# connectors.net
KiCad netlist of a schematic drawn in Altium Designer
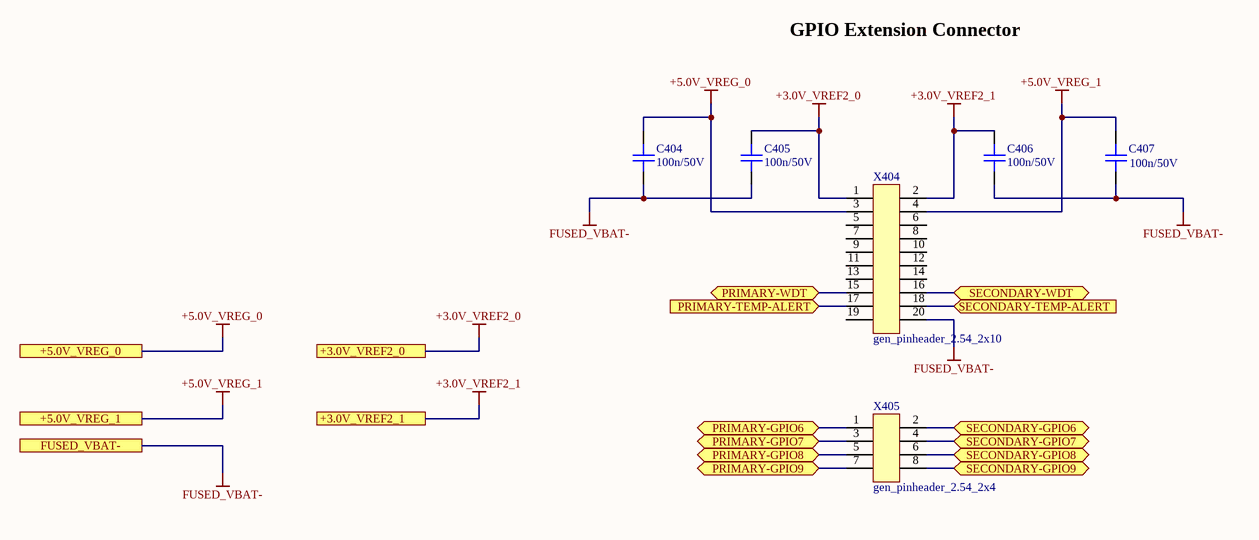
[diagram p0: connectors.SchDoc]

(export (version "E")
  (design (tool "Eeschema 10.0.6"))
  (components
    (comp (ref "C404")
      (value "100n/50V")
      (footprint "CAPC1608X08N")
      (description "MLCC")
      (fields (field (name "PART NUMBER") "gen_C_ceramic_100n_50V_X7R_0603"))
      (libsource (lib "OE750") (part "C"))
    )
    (comp (ref "C405")
      (value "100n/50V")
      (footprint "CAPC1608X08N")
      (description "MLCC")
      (fields (field (name "PART NUMBER") "gen_C_ceramic_100n_50V_X7R_0603"))
      (libsource (lib "OE750") (part "C"))
    )
    (comp (ref "C406")
      (value "100n/50V")
      (footprint "CAPC1608X08N")
      (description "MLCC")
      (fields (field (name "PART NUMBER") "gen_C_ceramic_100n_50V_X7R_0603"))
      (libsource (lib "OE750") (part "C"))
    )
    (comp (ref "C407")
      (value "100n/50V")
      (footprint "CAPC1608X08N")
      (description "MLCC")
      (fields (field (name "PART NUMBER") "gen_C_ceramic_100n_50V_X7R_0603"))
      (libsource (lib "OE750") (part "C"))
    )
    (comp (ref "X404")
      (value "gen_pinheader_2.54_2x10")
      (footprint "Pinheader_2.54_2x10")
      (description "Standard Pinheader, THD, gerade, 2.54mm, 2-reihig")
      (libsource (lib "OE750") (part "X2x10"))
    )
    (comp (ref "X405")
      (value "gen_pinheader_2.54_2x4")
      (footprint "Pinheader_2.54_2x4")
      (description "Standard Pinheader, THD, gerade, 2.54mm, 2-reihig")
      (libsource (lib "OE750") (part "X2x4"))
    )
  )
  (nets
    (net (code "1") (name "+3.0V_VREF2_0") (class "Default")
      (node (ref "C405") (pin "2") (pinfunction "2_2") (pintype "passive"))
      (node (ref "X404") (pin "1") (pintype "passive"))
    )
    (net (code "2") (name "+3.0V_VREF2_1") (class "Default")
      (node (ref "C406") (pin "2") (pinfunction "2_2") (pintype "passive"))
      (node (ref "X404") (pin "2") (pintype "passive"))
    )
    (net (code "3") (name "+5.0V_VREG_0") (class "Default")
      (node (ref "C404") (pin "2") (pinfunction "2_2") (pintype "passive"))
      (node (ref "X404") (pin "3") (pintype "passive"))
    )
    (net (code "4") (name "+5.0V_VREG_1") (class "Default")
      (node (ref "C407") (pin "2") (pinfunction "2_2") (pintype "passive"))
      (node (ref "X404") (pin "4") (pintype "passive"))
    )
    (net (code "5") (name "/PRIMARY-GPIO6") (class "Default")
      (node (ref "X405") (pin "1") (pintype "passive"))
    )
    (net (code "6") (name "/PRIMARY-GPIO7") (class "Default")
      (node (ref "X405") (pin "3") (pintype "passive"))
    )
    (net (code "7") (name "/PRIMARY-GPIO8") (class "Default")
      (node (ref "X405") (pin "5") (pintype "passive"))
    )
    (net (code "8") (name "/PRIMARY-GPIO9") (class "Default")
      (node (ref "X405") (pin "7") (pintype "passive"))
    )
    (net (code "9") (name "/PRIMARY-TEMP-ALERT") (class "Default")
      (node (ref "X404") (pin "17") (pintype "passive"))
    )
    (net (code "10") (name "/PRIMARY-WDT") (class "Default")
      (node (ref "X404") (pin "15") (pintype "passive"))
    )
    (net (code "11") (name "/SECONDARY-GPIO6") (class "Default")
      (node (ref "X405") (pin "2") (pintype "passive"))
    )
    (net (code "12") (name "/SECONDARY-GPIO7") (class "Default")
      (node (ref "X405") (pin "4") (pintype "passive"))
    )
    (net (code "13") (name "/SECONDARY-GPIO8") (class "Default")
      (node (ref "X405") (pin "6") (pintype "passive"))
    )
    (net (code "14") (name "/SECONDARY-GPIO9") (class "Default")
      (node (ref "X405") (pin "8") (pintype "passive"))
    )
    (net (code "15") (name "/SECONDARY-TEMP-ALERT") (class "Default")
      (node (ref "X404") (pin "18") (pintype "passive"))
    )
    (net (code "16") (name "/SECONDARY-WDT") (class "Default")
      (node (ref "X404") (pin "16") (pintype "passive"))
    )
    (net (code "17") (name "FUSED_VBAT-") (class "Default")
      (node (ref "C404") (pin "1") (pinfunction "1_1") (pintype "passive"))
      (node (ref "C405") (pin "1") (pinfunction "1_1") (pintype "passive"))
      (node (ref "C406") (pin "1") (pinfunction "1_1") (pintype "passive"))
      (node (ref "C407") (pin "1") (pinfunction "1_1") (pintype "passive"))
      (node (ref "X404") (pin "20") (pintype "passive"))
    )
    (net (code "18") (name "unconnected-(X404-Pad5)") (class "Default")
      (node (ref "X404") (pin "5") (pintype "passive"))
    )
    (net (code "19") (name "unconnected-(X404-Pad6)") (class "Default")
      (node (ref "X404") (pin "6") (pintype "passive"))
    )
    (net (code "20") (name "unconnected-(X404-Pad7)") (class "Default")
      (node (ref "X404") (pin "7") (pintype "passive"))
    )
    (net (code "21") (name "unconnected-(X404-Pad8)") (class "Default")
      (node (ref "X404") (pin "8") (pintype "passive"))
    )
    (net (code "22") (name "unconnected-(X404-Pad9)") (class "Default")
      (node (ref "X404") (pin "9") (pintype "passive"))
    )
    (net (code "23") (name "unconnected-(X404-Pad10)") (class "Default")
      (node (ref "X404") (pin "10") (pintype "passive"))
    )
    (net (code "24") (name "unconnected-(X404-Pad11)") (class "Default")
      (node (ref "X404") (pin "11") (pintype "passive"))
    )
    (net (code "25") (name "unconnected-(X404-Pad12)") (class "Default")
      (node (ref "X404") (pin "12") (pintype "passive"))
    )
    (net (code "26") (name "unconnected-(X404-Pad13)") (class "Default")
      (node (ref "X404") (pin "13") (pintype "passive"))
    )
    (net (code "27") (name "unconnected-(X404-Pad14)") (class "Default")
      (node (ref "X404") (pin "14") (pintype "passive"))
    )
    (net (code "28") (name "unconnected-(X404-Pad19)") (class "Default")
      (node (ref "X404") (pin "19") (pintype "passive"))
    )
  )
)
